# Sheet1.net
KiCad netlist of a schematic drawn in Altium Designer
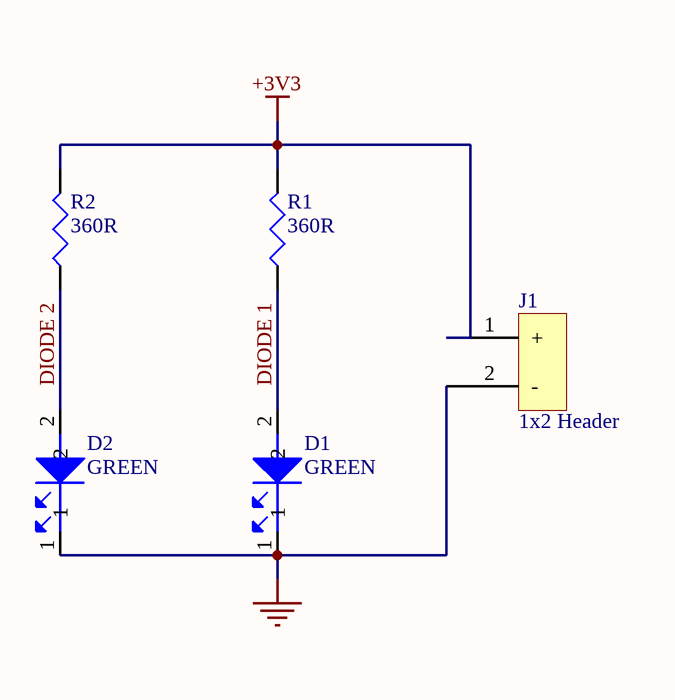
[diagram p0: Sheet1.SchDoc]

(export (version "E")
  (design (tool "Eeschema 10.0.6"))
  (components
    (comp (ref "D1")
      (value "GREEN")
      (footprint "LED0603")
      (description "LED SM 0603 3V -/1000/-MCD GREEN")
      (fields
        (field (name "MANUFACTURER") "Visual Communications")
        (field (name "MANUFACTURER PART NUMBER") "LSM0603453V")
      )
      (libsource (lib "Schlib1") (part "LSM0603453V"))
    )
    (comp (ref "D2")
      (value "GREEN")
      (footprint "LED0603")
      (description "LED SM 0603 3V -/1000/-MCD GREEN")
      (fields
        (field (name "MANUFACTURER") "Visual Communications")
        (field (name "MANUFACTURER PART NUMBER") "LSM0603453V")
      )
      (libsource (lib "Schlib1") (part "LSM0603453V"))
    )
    (comp (ref "J1")
      (value "1x2 Header")
      (footprint "HDR1x2")
      (description "CONN HEADER VERT 2POS 2.54MM")
      (fields (field (name "MANUFACTURER") "Molex") (field (name "MANUFACTURER PART NUMBER") "22-27-2021"))
      (libsource (lib "Schlib1") (part "22-27-2021"))
    )
    (comp (ref "R1")
      (value "360R")
      (footprint "R0805")
      (description "RES 360 OHM 1% 1/8W 0805")
      (fields
        (field (name "MANUFACTURER") "Yageo")
        (field (name "MANUFACTURER PART NUMBER") "RC0805FR-07360RL")
      )
      (libsource (lib "Schlib1") (part "AC0805FR-07360RL"))
    )
    (comp (ref "R2")
      (value "360R")
      (footprint "R0805")
      (description "RES 360 OHM 1% 1/8W 0805")
      (fields
        (field (name "MANUFACTURER") "Yageo")
        (field (name "MANUFACTURER PART NUMBER") "RC0805FR-07360RL")
      )
      (libsource (lib "Schlib1") (part "AC0805FR-07360RL"))
    )
  )
  (nets
    (net (code "1") (name "+3V3") (class "Default")
      (node (ref "J1") (pin "1") (pinfunction "+_1") (pintype "passive"))
      (node (ref "R1") (pin "2") (pinfunction "2_2") (pintype "passive"))
      (node (ref "R2") (pin "2") (pinfunction "2_2") (pintype "passive"))
    )
    (net (code "2") (name "/DIODE 1") (class "Default")
      (node (ref "D1") (pin "2") (pinfunction "2_2") (pintype "passive"))
      (node (ref "R1") (pin "1") (pinfunction "1_1") (pintype "passive"))
    )
    (net (code "3") (name "/DIODE 2") (class "Default")
      (node (ref "D2") (pin "2") (pinfunction "2_2") (pintype "passive"))
      (node (ref "R2") (pin "1") (pinfunction "1_1") (pintype "passive"))
    )
    (net (code "4") (name "GND") (class "Default")
      (node (ref "D1") (pin "1") (pinfunction "1_1") (pintype "passive"))
      (node (ref "D2") (pin "1") (pinfunction "1_1") (pintype "passive"))
      (node (ref "J1") (pin "2") (pinfunction "-_2") (pintype "passive"))
    )
  )
)
